# bot.net
KiCad netlist of a schematic drawn in Altium Designer
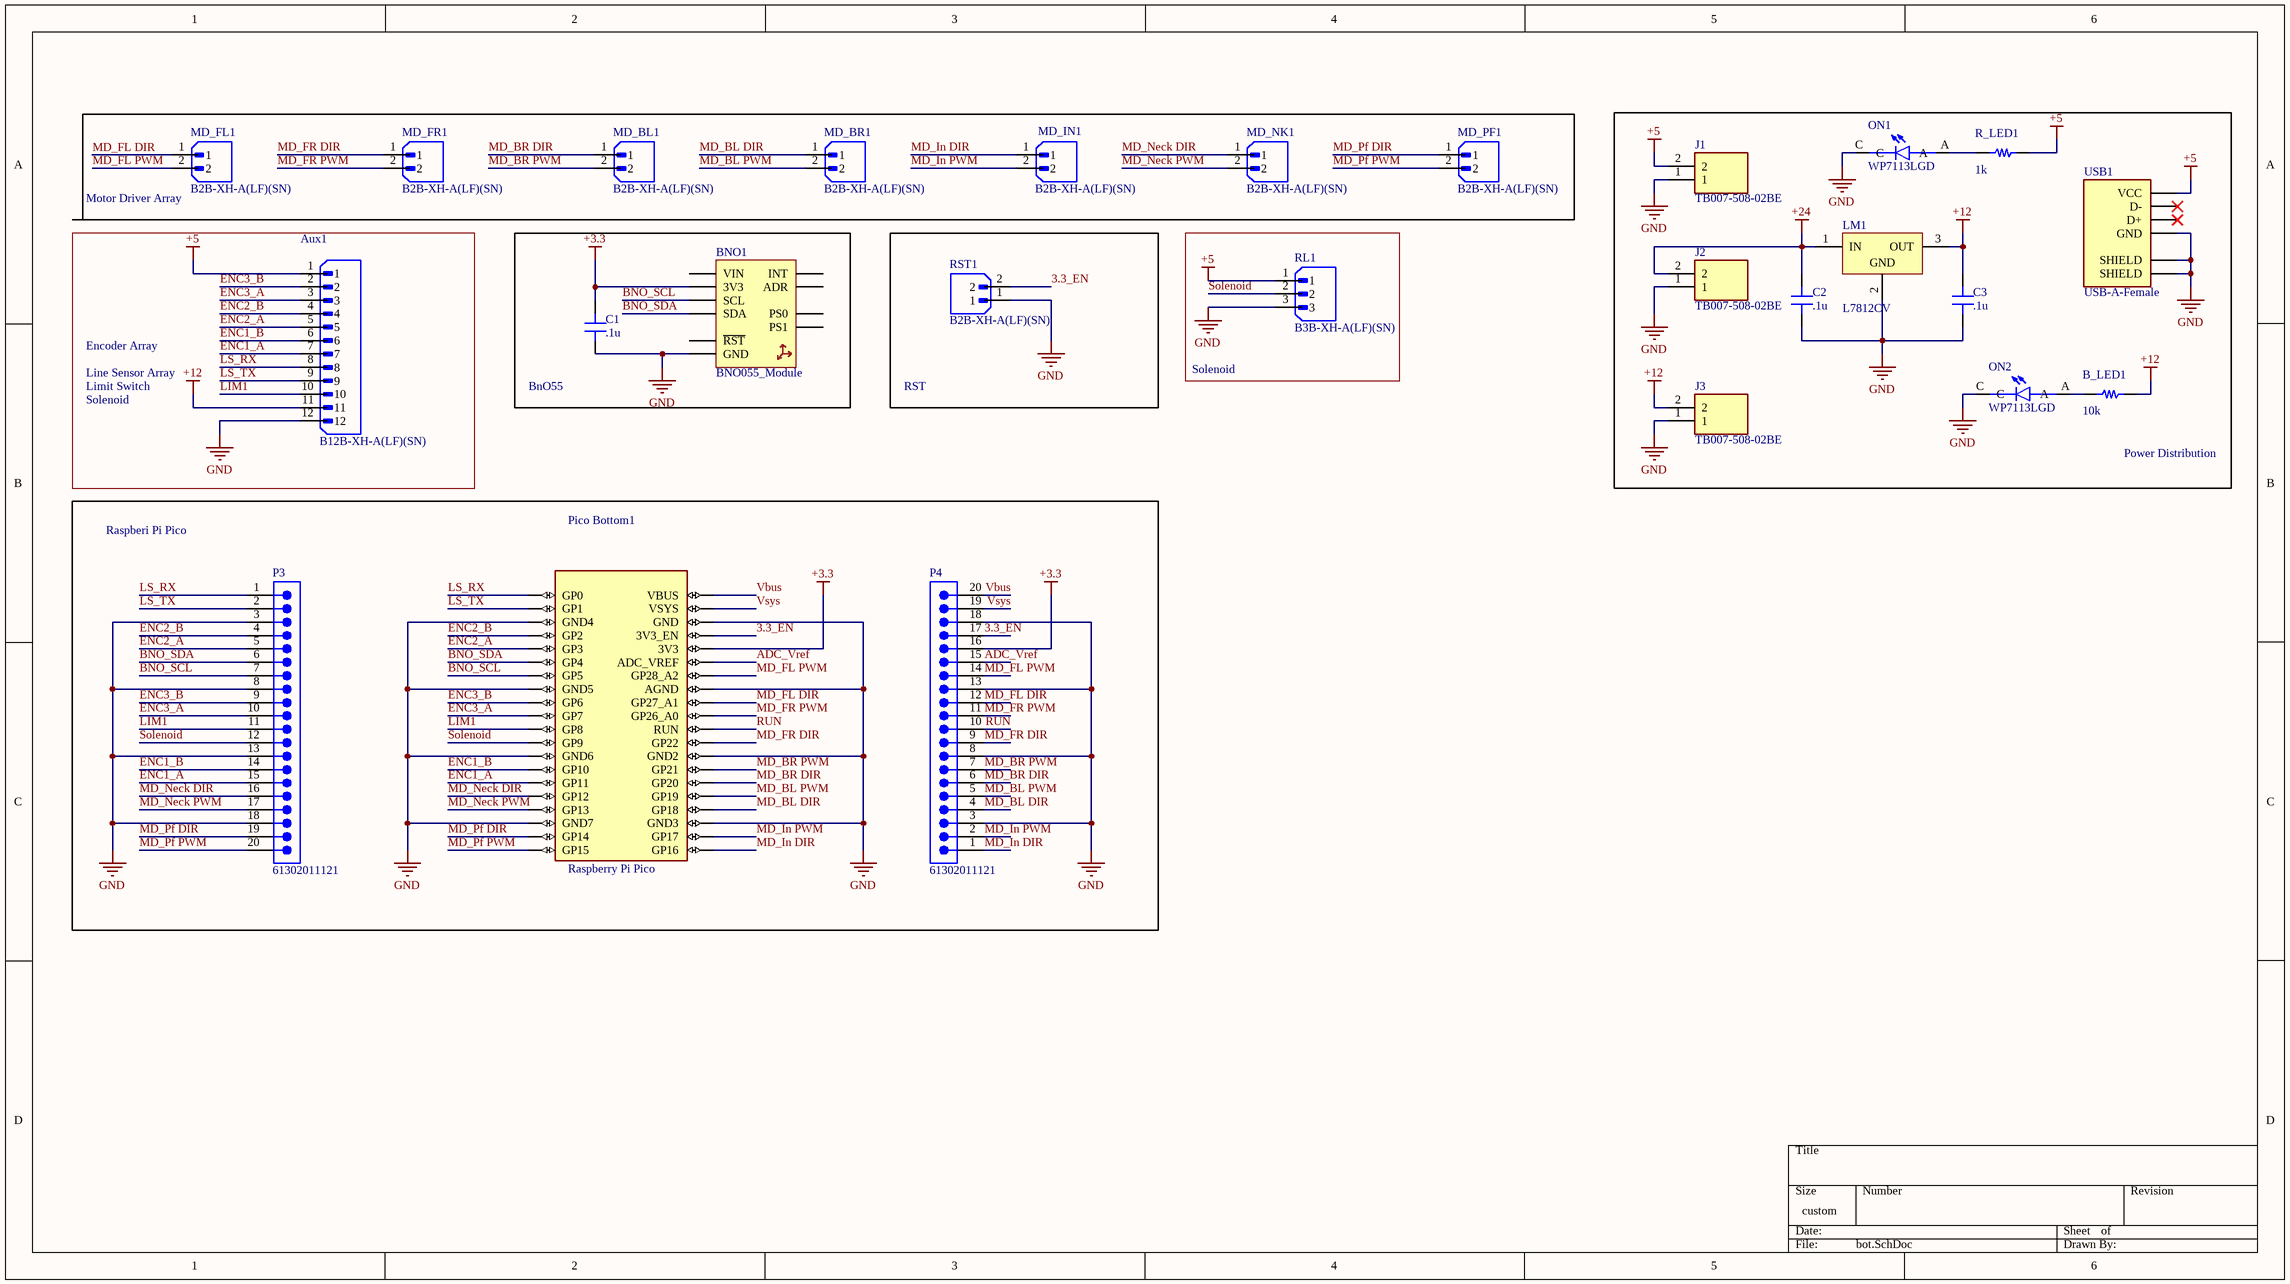
[diagram p0: bot.SchDoc]

(export (version "E")
  (design (tool "Eeschema 10.0.6"))
  (components
    (comp (ref "Aux1")
      (value "B12B-XH-A(LF)(SN)")
      (footprint "JST_B12B-XH-A(LF)(SN)")
      (description "Connector Header Through Hole 12 position 0.098 (2.50mm)")
      (fields (field (name "MF") "JST Sales"))
      (libsource (lib "CSD Robocon Workspace") (part "B12B-XH-A(LF)(SN)"))
    )
    (comp (ref "BNO1")
      (value "BNO055_Module")
      (footprint "BNO055_Modiule-Footprint-1")
      (description "Module for Bosch BNO055 9 axis precision IMU")
      (libsource (lib "CSD Robocon Workspace") (part "BNO055_Modiule-Symbol-1"))
    )
    (comp (ref "B_LED1")
      (value "10k")
      (footprint "generic_res_footprint")
      (description "Generic through hole resistor")
      (libsource (lib "CSD Robocon Workspace") (part "generic_res"))
    )
    (comp (ref "C1")
      (value ".1u")
      (footprint "generic_cap")
      (description "Generic Ceramic Capacitor")
      (fields (field (name "MP") "RDER71H472K0K1H03B"))
      (libsource (lib "CSD Robocon Workspace") (part "generic_cap"))
    )
    (comp (ref "C2")
      (value ".1u")
      (footprint "generic_cap")
      (description "Generic Ceramic Capacitor")
      (fields (field (name "MP") "RDER71H472K0K1H03B"))
      (libsource (lib "CSD Robocon Workspace") (part "generic_cap"))
    )
    (comp (ref "C3")
      (value ".1u")
      (footprint "generic_cap")
      (description "Generic Ceramic Capacitor")
      (fields (field (name "MP") "RDER71H472K0K1H03B"))
      (libsource (lib "CSD Robocon Workspace") (part "generic_cap"))
    )
    (comp (ref "J1")
      (value "TB007-508-02BE")
      (footprint "CUI_TB007-508-02BE")
      (description "Barrier Strip Terminal Block")
      (fields (field (name "MF") "{'manufacturer': u'CUI'}"))
      (libsource (lib "CSD Robocon Workspace") (part "TB007-508-02BE"))
    )
    (comp (ref "J2")
      (value "TB007-508-02BE")
      (footprint "CUI_TB007-508-02BE")
      (description "Barrier Strip Terminal Block")
      (fields (field (name "MF") "{'manufacturer': u'CUI'}"))
      (libsource (lib "CSD Robocon Workspace") (part "TB007-508-02BE"))
    )
    (comp (ref "J3")
      (value "TB007-508-02BE")
      (footprint "CUI_TB007-508-02BE")
      (description "Barrier Strip Terminal Block")
      (fields (field (name "MF") "{'manufacturer': u'CUI'}"))
      (libsource (lib "CSD Robocon Workspace") (part "TB007-508-02BE"))
    )
    (comp (ref "LM1")
      (value "L7812CV")
      (footprint "L7812_footprint")
      (description "Fixed Positive Standard Regulator, 12V BIPolar, PSFM3")
      (libsource (lib "CSD Robocon Workspace") (part "l7812_symbol"))
    )
    (comp (ref "MD_BL1")
      (value "B2B-XH-A(LF)(SN)")
      (footprint "JST_B2B-XH-A(LF)(SN)")
      (description "Connector Header Through Hole 2 position 0.098 (2.50mm)")
      (fields (field (name "MF") "JST Sales America Inc."))
      (libsource (lib "CSD Robocon Workspace") (part "B2B-XH-A(LF)(SN)"))
    )
    (comp (ref "MD_BR1")
      (value "B2B-XH-A(LF)(SN)")
      (footprint "JST_B2B-XH-A(LF)(SN)")
      (description "Connector Header Through Hole 2 position 0.098 (2.50mm)")
      (fields (field (name "MF") "JST Sales America Inc."))
      (libsource (lib "CSD Robocon Workspace") (part "B2B-XH-A(LF)(SN)"))
    )
    (comp (ref "MD_FL1")
      (value "B2B-XH-A(LF)(SN)")
      (footprint "JST_B2B-XH-A(LF)(SN)")
      (description "Connector Header Through Hole 2 position 0.098 (2.50mm)")
      (fields (field (name "MF") "JST Sales America Inc."))
      (libsource (lib "CSD Robocon Workspace") (part "B2B-XH-A(LF)(SN)"))
    )
    (comp (ref "MD_FR1")
      (value "B2B-XH-A(LF)(SN)")
      (footprint "JST_B2B-XH-A(LF)(SN)")
      (description "Connector Header Through Hole 2 position 0.098 (2.50mm)")
      (fields (field (name "MF") "JST Sales America Inc."))
      (libsource (lib "CSD Robocon Workspace") (part "B2B-XH-A(LF)(SN)"))
    )
    (comp (ref "MD_IN1")
      (value "B2B-XH-A(LF)(SN)")
      (footprint "JST_B2B-XH-A(LF)(SN)")
      (description "Connector Header Through Hole 2 position 0.098 (2.50mm)")
      (fields (field (name "MF") "JST Sales America Inc."))
      (libsource (lib "CSD Robocon Workspace") (part "B2B-XH-A(LF)(SN)"))
    )
    (comp (ref "MD_NK1")
      (value "B2B-XH-A(LF)(SN)")
      (footprint "JST_B2B-XH-A(LF)(SN)")
      (description "Connector Header Through Hole 2 position 0.098 (2.50mm)")
      (fields (field (name "MF") "JST Sales America Inc."))
      (libsource (lib "CSD Robocon Workspace") (part "B2B-XH-A(LF)(SN)"))
    )
    (comp (ref "MD_PF1")
      (value "B2B-XH-A(LF)(SN)")
      (footprint "JST_B2B-XH-A(LF)(SN)")
      (description "Connector Header Through Hole 2 position 0.098 (2.50mm)")
      (fields (field (name "MF") "JST Sales America Inc."))
      (libsource (lib "") (part "B2B-XH-A(LF)(SN)_2"))
    )
    (comp (ref "ON1")
      (value "WP7113LGD")
      (footprint "LED_WP7113LGD")
      (description "Green 568nm LED Indication - Discrete 1.9V Radial")
      (fields (field (name "MF") "Kingbright"))
      (libsource (lib "CSD Robocon Workspace") (part "WP7113LGD"))
    )
    (comp (ref "ON2")
      (value "WP7113LGD")
      (footprint "LED_WP7113LGD")
      (description "Green 568nm LED Indication - Discrete 1.9V Radial")
      (fields (field (name "MF") "Kingbright"))
      (libsource (lib "CSD Robocon Workspace") (part "WP7113LGD"))
    )
    (comp (ref "P3")
      (value "61302011121")
      (footprint "61302011121")
      (description "WR-PHD Pin Header, THT, Vertical, pitch 2.54mm, 1 Row, 20P")
      (fields (field (name "MANUFACTURER") "Wurth Elektronik"))
      (libsource (lib "CSD Robocon Workspace") (part "62002011121"))
    )
    (comp (ref "P4")
      (value "61302011121")
      (footprint "61302011121")
      (description "WR-PHD Pin Header, THT, Vertical, pitch 2.54mm, 1 Row, 20P")
      (fields (field (name "MANUFACTURER") "Wurth Elektronik"))
      (libsource (lib "CSD Robocon Workspace") (part "62002011121"))
    )
    (comp (ref "Pico Bottom1")
      (value "Raspberry Pi Pico")
      (footprint "RASPBERRY_PI_PICO")
      (description "Raspberry Pi Board, Arm Cortex-M0+")
      (fields (field (name "MF") "Raspberry Pi") (field (name "MP") "RASPBERRY PI PICO"))
      (libsource (lib "CSD Robocon Workspace") (part "Raspberry Pi Pico"))
    )
    (comp (ref "RL1")
      (value "B3B-XH-A(LF)(SN)")
      (footprint "JST_B3B-XH-A(LF)(SN)")
      (description "Connector Header Through Hole 3 position 0.098 (2.50mm)")
      (fields (field (name "MF") "JST Sales"))
      (libsource (lib "CSD Robocon Workspace") (part "B3B-XH-A(LF)(SN)"))
    )
    (comp (ref "RST1")
      (value "B2B-XH-A(LF)(SN)")
      (footprint "JST_B2B-XH-A(LF)(SN)")
      (description "Connector Header Through Hole 2 position 0.098 (2.50mm)")
      (fields (field (name "MF") "JST Sales America Inc."))
      (libsource (lib "") (part "B2B-XH-A(LF)(SN)_1"))
    )
    (comp (ref "R_LED1")
      (value "1k")
      (footprint "generic_res_footprint")
      (description "Generic through hole resistor")
      (libsource (lib "CSD Robocon Workspace") (part "generic_res"))
    )
    (comp (ref "USB1")
      (value "USB-A-Female")
      (footprint "CUI_UJ2-AH-4-TH")
      (description "Type A, USB 2.0, 1 A, Right Angle, Through Hole, USB Receptacle")
      (fields (field (name "MF") "CUI Devices") (field (name "MP") "UJ2-AH-4-TH"))
      (libsource (lib "CSD Robocon Workspace") (part "UJ2-AH-4-TH"))
    )
  )
  (nets
    (net (code "1") (name "+3.3") (class "Default")
      (node (ref "BNO1") (pin "1") (pinfunction "3V3_1") (pintype "passive"))
      (node (ref "C1") (pin "2") (pinfunction "2_2") (pintype "passive"))
      (node (ref "P4") (pin "16") (pinfunction "16_16") (pintype "passive"))
      (node (ref "Pico Bottom1") (pin "3V3") (pinfunction "3V3_3V3") (pintype "bidirectional"))
    )
    (net (code "2") (name "+5") (class "Default")
      (node (ref "Aux1") (pin "1") (pinfunction "1_1") (pintype "passive"))
      (node (ref "J1") (pin "2") (pinfunction "2_2") (pintype "passive"))
      (node (ref "RL1") (pin "1") (pinfunction "1_1") (pintype "passive"))
      (node (ref "R_LED1") (pin "2") (pinfunction "2_2") (pintype "passive"))
      (node (ref "USB1") (pin "1") (pinfunction "VCC_1") (pintype "passive"))
    )
    (net (code "3") (name "+12") (class "Default")
      (node (ref "Aux1") (pin "11") (pinfunction "11_11") (pintype "passive"))
      (node (ref "B_LED1") (pin "2") (pinfunction "2_2") (pintype "passive"))
      (node (ref "C3") (pin "2") (pinfunction "2_2") (pintype "passive"))
      (node (ref "J3") (pin "2") (pinfunction "2_2") (pintype "passive"))
      (node (ref "LM1") (pin "3") (pinfunction "OUT_3") (pintype "power_in"))
    )
    (net (code "4") (name "+24") (class "Default")
      (node (ref "C2") (pin "2") (pinfunction "2_2") (pintype "passive"))
      (node (ref "J2") (pin "2") (pinfunction "2_2") (pintype "passive"))
      (node (ref "LM1") (pin "1") (pinfunction "IN_1") (pintype "power_in"))
    )
    (net (code "5") (name "/3.3_EN") (class "Default")
      (node (ref "P4") (pin "17") (pinfunction "17_17") (pintype "passive"))
      (node (ref "Pico Bottom1") (pin "3V3_EN") (pinfunction "3V3_EN_3V3_EN") (pintype "bidirectional"))
      (node (ref "RST1") (pin "2") (pinfunction "2_2") (pintype "passive"))
    )
    (net (code "6") (name "/ADC_Vref") (class "Default")
      (node (ref "P4") (pin "15") (pinfunction "15_15") (pintype "passive"))
      (node (ref "Pico Bottom1") (pin "ADC_VREF") (pinfunction "ADC_VREF_ADC_VREF") (pintype "bidirectional"))
    )
    (net (code "7") (name "/BNO_SCL") (class "Default")
      (node (ref "BNO1") (pin "2") (pinfunction "SCL_2") (pintype "passive"))
      (node (ref "P3") (pin "7") (pinfunction "7_7") (pintype "passive"))
      (node (ref "Pico Bottom1") (pin "GP5") (pinfunction "GP5_GP5") (pintype "bidirectional"))
    )
    (net (code "8") (name "/BNO_SDA") (class "Default")
      (node (ref "BNO1") (pin "3") (pinfunction "SDA_3") (pintype "passive"))
      (node (ref "P3") (pin "6") (pinfunction "6_6") (pintype "passive"))
      (node (ref "Pico Bottom1") (pin "GP4") (pinfunction "GP4_GP4") (pintype "bidirectional"))
    )
    (net (code "9") (name "/ENC1_A") (class "Default")
      (node (ref "Aux1") (pin "7") (pinfunction "7_7") (pintype "passive"))
      (node (ref "P3") (pin "15") (pinfunction "15_15") (pintype "passive"))
      (node (ref "Pico Bottom1") (pin "GP11") (pinfunction "GP11_GP11") (pintype "bidirectional"))
    )
    (net (code "10") (name "/ENC1_B") (class "Default")
      (node (ref "Aux1") (pin "6") (pinfunction "6_6") (pintype "passive"))
      (node (ref "P3") (pin "14") (pinfunction "14_14") (pintype "passive"))
      (node (ref "Pico Bottom1") (pin "GP10") (pinfunction "GP10_GP10") (pintype "bidirectional"))
    )
    (net (code "11") (name "/ENC2_A") (class "Default")
      (node (ref "Aux1") (pin "5") (pinfunction "5_5") (pintype "passive"))
      (node (ref "P3") (pin "5") (pinfunction "5_5") (pintype "passive"))
      (node (ref "Pico Bottom1") (pin "GP3") (pinfunction "GP3_GP3") (pintype "bidirectional"))
    )
    (net (code "12") (name "/ENC2_B") (class "Default")
      (node (ref "Aux1") (pin "4") (pinfunction "4_4") (pintype "passive"))
      (node (ref "P3") (pin "4") (pinfunction "4_4") (pintype "passive"))
      (node (ref "Pico Bottom1") (pin "GP2") (pinfunction "GP2_GP2") (pintype "bidirectional"))
    )
    (net (code "13") (name "/ENC3_A") (class "Default")
      (node (ref "Aux1") (pin "3") (pinfunction "3_3") (pintype "passive"))
      (node (ref "P3") (pin "10") (pinfunction "10_10") (pintype "passive"))
      (node (ref "Pico Bottom1") (pin "GP7") (pinfunction "GP7_GP7") (pintype "bidirectional"))
    )
    (net (code "14") (name "/ENC3_B") (class "Default")
      (node (ref "Aux1") (pin "2") (pinfunction "2_2") (pintype "passive"))
      (node (ref "P3") (pin "9") (pinfunction "9_9") (pintype "passive"))
      (node (ref "Pico Bottom1") (pin "GP6") (pinfunction "GP6_GP6") (pintype "bidirectional"))
    )
    (net (code "15") (name "/LIM1") (class "Default")
      (node (ref "Aux1") (pin "10") (pinfunction "10_10") (pintype "passive"))
      (node (ref "P3") (pin "11") (pinfunction "11_11") (pintype "passive"))
      (node (ref "Pico Bottom1") (pin "GP8") (pinfunction "GP8_GP8") (pintype "bidirectional"))
    )
    (net (code "16") (name "/LS_RX") (class "Default")
      (node (ref "Aux1") (pin "8") (pinfunction "8_8") (pintype "passive"))
      (node (ref "P3") (pin "1") (pinfunction "1_1") (pintype "passive"))
      (node (ref "Pico Bottom1") (pin "GP0") (pinfunction "GP0_GP0") (pintype "bidirectional"))
    )
    (net (code "17") (name "/LS_TX") (class "Default")
      (node (ref "Aux1") (pin "9") (pinfunction "9_9") (pintype "passive"))
      (node (ref "P3") (pin "2") (pinfunction "2_2") (pintype "passive"))
      (node (ref "Pico Bottom1") (pin "GP1") (pinfunction "GP1_GP1") (pintype "bidirectional"))
    )
    (net (code "18") (name "/MD_BL DIR") (class "Default")
      (node (ref "MD_BR1") (pin "1") (pinfunction "1_1") (pintype "passive"))
      (node (ref "P4") (pin "4") (pinfunction "4_4") (pintype "passive"))
      (node (ref "Pico Bottom1") (pin "GP18") (pinfunction "GP18_GP18") (pintype "bidirectional"))
    )
    (net (code "19") (name "/MD_BL PWM") (class "Default")
      (node (ref "MD_BR1") (pin "2") (pinfunction "2_2") (pintype "passive"))
      (node (ref "P4") (pin "5") (pinfunction "5_5") (pintype "passive"))
      (node (ref "Pico Bottom1") (pin "GP19") (pinfunction "GP19_GP19") (pintype "bidirectional"))
    )
    (net (code "20") (name "/MD_BR DIR") (class "Default")
      (node (ref "MD_BL1") (pin "1") (pinfunction "1_1") (pintype "passive"))
      (node (ref "P4") (pin "6") (pinfunction "6_6") (pintype "passive"))
      (node (ref "Pico Bottom1") (pin "GP20") (pinfunction "GP20_GP20") (pintype "bidirectional"))
    )
    (net (code "21") (name "/MD_BR PWM") (class "Default")
      (node (ref "MD_BL1") (pin "2") (pinfunction "2_2") (pintype "passive"))
      (node (ref "P4") (pin "7") (pinfunction "7_7") (pintype "passive"))
      (node (ref "Pico Bottom1") (pin "GP21") (pinfunction "GP21_GP21") (pintype "bidirectional"))
    )
    (net (code "22") (name "/MD_FL DIR") (class "Default")
      (node (ref "MD_FL1") (pin "1") (pinfunction "1_1") (pintype "passive"))
      (node (ref "P4") (pin "12") (pinfunction "12_12") (pintype "passive"))
      (node (ref "Pico Bottom1") (pin "GP27_A1") (pinfunction "GP27_A1_GP27_A1") (pintype "bidirectional"))
    )
    (net (code "23") (name "/MD_FL PWM") (class "Default")
      (node (ref "MD_FL1") (pin "2") (pinfunction "2_2") (pintype "passive"))
      (node (ref "P4") (pin "14") (pinfunction "14_14") (pintype "passive"))
      (node (ref "Pico Bottom1") (pin "GP28_A2") (pinfunction "GP28_A2_GP28_A2") (pintype "bidirectional"))
    )
    (net (code "24") (name "/MD_FR DIR") (class "Default")
      (node (ref "MD_FR1") (pin "1") (pinfunction "1_1") (pintype "passive"))
      (node (ref "P4") (pin "9") (pinfunction "9_9") (pintype "passive"))
      (node (ref "Pico Bottom1") (pin "GP22") (pinfunction "GP22_GP22") (pintype "bidirectional"))
    )
    (net (code "25") (name "/MD_FR PWM") (class "Default")
      (node (ref "MD_FR1") (pin "2") (pinfunction "2_2") (pintype "passive"))
      (node (ref "P4") (pin "11") (pinfunction "11_11") (pintype "passive"))
      (node (ref "Pico Bottom1") (pin "GP26_A0") (pinfunction "GP26_A0_GP26_A0") (pintype "bidirectional"))
    )
    (net (code "26") (name "/MD_In DIR") (class "Default")
      (node (ref "MD_IN1") (pin "1") (pinfunction "1_1") (pintype "passive"))
      (node (ref "P4") (pin "1") (pinfunction "1_1") (pintype "passive"))
      (node (ref "Pico Bottom1") (pin "GP16") (pinfunction "GP16_GP16") (pintype "bidirectional"))
    )
    (net (code "27") (name "/MD_In PWM") (class "Default")
      (node (ref "MD_IN1") (pin "2") (pinfunction "2_2") (pintype "passive"))
      (node (ref "P4") (pin "2") (pinfunction "2_2") (pintype "passive"))
      (node (ref "Pico Bottom1") (pin "GP17") (pinfunction "GP17_GP17") (pintype "bidirectional"))
    )
    (net (code "28") (name "/MD_Neck DIR") (class "Default")
      (node (ref "MD_NK1") (pin "1") (pinfunction "1_1") (pintype "passive"))
      (node (ref "P3") (pin "16") (pinfunction "16_16") (pintype "passive"))
      (node (ref "Pico Bottom1") (pin "GP12") (pinfunction "GP12_GP12") (pintype "bidirectional"))
    )
    (net (code "29") (name "/MD_Neck PWM") (class "Default")
      (node (ref "MD_NK1") (pin "2") (pinfunction "2_2") (pintype "passive"))
      (node (ref "P3") (pin "17") (pinfunction "17_17") (pintype "passive"))
      (node (ref "Pico Bottom1") (pin "GP13") (pinfunction "GP13_GP13") (pintype "bidirectional"))
    )
    (net (code "30") (name "/MD_Pf DIR") (class "Default")
      (node (ref "MD_PF1") (pin "1") (pinfunction "1_1") (pintype "passive"))
      (node (ref "P3") (pin "19") (pinfunction "19_19") (pintype "passive"))
      (node (ref "Pico Bottom1") (pin "GP14") (pinfunction "GP14_GP14") (pintype "bidirectional"))
    )
    (net (code "31") (name "/MD_Pf PWM") (class "Default")
      (node (ref "MD_PF1") (pin "2") (pinfunction "2_2") (pintype "passive"))
      (node (ref "P3") (pin "20") (pinfunction "20_20") (pintype "passive"))
      (node (ref "Pico Bottom1") (pin "GP15") (pinfunction "GP15_GP15") (pintype "bidirectional"))
    )
    (net (code "32") (name "/RUN") (class "Default")
      (node (ref "P4") (pin "10") (pinfunction "10_10") (pintype "passive"))
      (node (ref "Pico Bottom1") (pin "RUN") (pinfunction "RUN_RUN") (pintype "bidirectional"))
    )
    (net (code "33") (name "/Solenoid") (class "Default")
      (node (ref "P3") (pin "12") (pinfunction "12_12") (pintype "passive"))
      (node (ref "Pico Bottom1") (pin "GP9") (pinfunction "GP9_GP9") (pintype "bidirectional"))
      (node (ref "RL1") (pin "2") (pinfunction "2_2") (pintype "passive"))
    )
    (net (code "34") (name "/Vbus") (class "Default")
      (node (ref "P4") (pin "20") (pinfunction "20_20") (pintype "passive"))
      (node (ref "Pico Bottom1") (pin "VBUS") (pinfunction "VBUS_VBUS") (pintype "bidirectional"))
    )
    (net (code "35") (name "/Vsys") (class "Default")
      (node (ref "P4") (pin "19") (pinfunction "19_19") (pintype "passive"))
      (node (ref "Pico Bottom1") (pin "VSYS") (pinfunction "VSYS_VSYS") (pintype "bidirectional"))
    )
    (net (code "36") (name "GND") (class "Default")
      (node (ref "Aux1") (pin "12") (pinfunction "12_12") (pintype "passive"))
      (node (ref "BNO1") (pin "5") (pinfunction "GND_5") (pintype "passive"))
      (node (ref "C1") (pin "1") (pinfunction "1_1") (pintype "passive"))
      (node (ref "C2") (pin "1") (pinfunction "1_1") (pintype "passive"))
      (node (ref "C3") (pin "1") (pinfunction "1_1") (pintype "passive"))
      (node (ref "J1") (pin "1") (pinfunction "1_1") (pintype "passive"))
      (node (ref "J2") (pin "1") (pinfunction "1_1") (pintype "passive"))
      (node (ref "J3") (pin "1") (pinfunction "1_1") (pintype "passive"))
      (node (ref "LM1") (pin "2") (pinfunction "GND_2") (pintype "power_in"))
      (node (ref "ON1") (pin "C") (pinfunction "C_C") (pintype "passive"))
      (node (ref "ON2") (pin "C") (pinfunction "C_C") (pintype "passive"))
      (node (ref "P3") (pin "13") (pinfunction "13_13") (pintype "passive"))
      (node (ref "P3") (pin "18") (pinfunction "18_18") (pintype "passive"))
      (node (ref "P3") (pin "3") (pinfunction "3_3") (pintype "passive"))
      (node (ref "P3") (pin "8") (pinfunction "8_8") (pintype "passive"))
      (node (ref "P4") (pin "13") (pinfunction "13_13") (pintype "passive"))
      (node (ref "P4") (pin "18") (pinfunction "18_18") (pintype "passive"))
      (node (ref "P4") (pin "3") (pinfunction "3_3") (pintype "passive"))
      (node (ref "P4") (pin "8") (pinfunction "8_8") (pintype "passive"))
      (node (ref "Pico Bottom1") (pin "AGND") (pinfunction "AGND_AGND") (pintype "bidirectional"))
      (node (ref "Pico Bottom1") (pin "GND") (pinfunction "GND_GND") (pintype "bidirectional"))
      (node (ref "Pico Bottom1") (pin "GND2") (pinfunction "GND2_GND2") (pintype "bidirectional"))
      (node (ref "Pico Bottom1") (pin "GND3") (pinfunction "GND3_GND3") (pintype "bidirectional"))
      (node (ref "Pico Bottom1") (pin "GND4") (pinfunction "GND4_GND4") (pintype "bidirectional"))
      (node (ref "Pico Bottom1") (pin "GND5") (pinfunction "GND5_GND5") (pintype "bidirectional"))
      (node (ref "Pico Bottom1") (pin "GND6") (pinfunction "GND6_GND6") (pintype "bidirectional"))
      (node (ref "Pico Bottom1") (pin "GND7") (pinfunction "GND7_GND7") (pintype "bidirectional"))
      (node (ref "RL1") (pin "3") (pinfunction "3_3") (pintype "passive"))
      (node (ref "RST1") (pin "1") (pinfunction "1_1") (pintype "passive"))
      (node (ref "USB1") (pin "4") (pinfunction "GND_4") (pintype "passive"))
      (node (ref "USB1") (pin "SH1") (pinfunction "SHIELD_SH1") (pintype "passive"))
      (node (ref "USB1") (pin "SH2") (pinfunction "SHIELD_SH2") (pintype "passive"))
    )
    (net (code "37") (name "Net-(B_LED1-Pad1)") (class "Default")
      (node (ref "B_LED1") (pin "1") (pinfunction "1_1") (pintype "passive"))
      (node (ref "ON2") (pin "A") (pinfunction "A_A") (pintype "passive"))
    )
    (net (code "38") (name "Net-(ON1-PadA)") (class "Default")
      (node (ref "ON1") (pin "A") (pinfunction "A_A") (pintype "passive"))
      (node (ref "R_LED1") (pin "1") (pinfunction "1_1") (pintype "passive"))
    )
    (net (code "39") (name "unconnected-(BNO1-ADR-Pad7)") (class "Default")
      (node (ref "BNO1") (pin "7") (pinfunction "ADR_7") (pintype "passive"))
    )
    (net (code "40") (name "unconnected-(BNO1-INT-Pad6)") (class "Default")
      (node (ref "BNO1") (pin "6") (pinfunction "INT_6") (pintype "passive"))
    )
    (net (code "41") (name "unconnected-(BNO1-PS0-Pad8)") (class "Default")
      (node (ref "BNO1") (pin "8") (pinfunction "PS0_8") (pintype "passive"))
    )
    (net (code "42") (name "unconnected-(BNO1-PS1-Pad9)") (class "Default")
      (node (ref "BNO1") (pin "9") (pinfunction "PS1_9") (pintype "passive"))
    )
    (net (code "43") (name "unconnected-(BNO1-VIN-Pad0)") (class "Default")
      (node (ref "BNO1") (pin "0") (pinfunction "VIN_0") (pintype "passive"))
    )
    (net (code "44") (name "unconnected-(BNO1-~{RST}-Pad4)") (class "Default")
      (node (ref "BNO1") (pin "4") (pinfunction "~{RST}_4") (pintype "passive"))
    )
    (net (code "45") (name "unconnected-(USB1-D+-Pad3)") (class "Default")
      (node (ref "USB1") (pin "3") (pinfunction "D+_3") (pintype "passive+no_connect"))
    )
    (net (code "46") (name "unconnected-(USB1-D--Pad2)") (class "Default")
      (node (ref "USB1") (pin "2") (pinfunction "D-_2") (pintype "passive+no_connect"))
    )
  )
)
